# 03-mcu1.net
KiCad netlist of a schematic drawn in Altium Designer
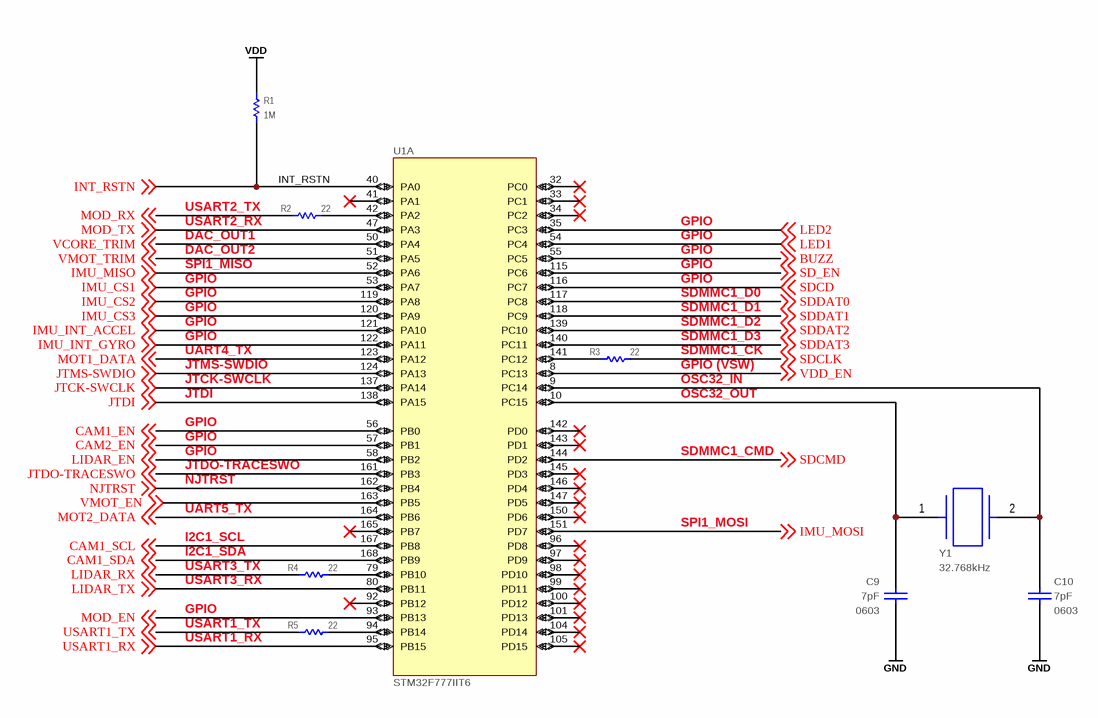
[diagram p0: 03-mcu1.SchDoc]

(export (version "E")
  (design (tool "Eeschema 10.0.6"))
  (components
    (comp (ref "C9")
      (value "7pF")
      (footprint "generic:CAPC160X80X90L20N")
      (description "Ceramic Capacitor 7pF +/-0.25pF 0603")
      (fields
        (field (name "MANUFACTURER") "Samsung")
        (field (name "TOLERANCE") "+/-0.25pF")
        (field (name "PACKAGE") "0603")
      )
      (libsource (lib "vishay") (part "CAP"))
    )
    (comp (ref "C10")
      (value "7pF")
      (footprint "generic:CAPC160X80X90L20N")
      (description "Ceramic Capacitor 7pF +/-0.25pF 0603")
      (fields
        (field (name "MANUFACTURER") "Samsung")
        (field (name "TOLERANCE") "+/-0.25pF")
        (field (name "PACKAGE") "0603")
      )
      (libsource (lib "vishay") (part "CAP"))
    )
    (comp (ref "R1")
      (value "1M")
      (footprint "RESC2012X70N")
      (description "Thick Film Resistor 1M ±1% 0805")
      (fields (field (name "MANUFACTURER") "Panasonic") (field (name "TOLERANCE") "±1%"))
      (libsource (lib "Graviton") (part "RES 0402"))
    )
    (comp (ref "R2")
      (value "22")
      (footprint "RESC2012X70N")
      (description "Thick Film Resistor 22 ±1% 0805")
      (fields (field (name "MANUFACTURER") "Panasonic") (field (name "TOLERANCE") "±1%"))
      (libsource (lib "Graviton") (part "RES 0402"))
    )
    (comp (ref "R3")
      (value "22")
      (footprint "RESC2012X70N")
      (description "Thick Film Resistor 22 ±1% 0805")
      (fields (field (name "MANUFACTURER") "Panasonic") (field (name "TOLERANCE") "±1%"))
      (libsource (lib "Graviton") (part "RES 0402"))
    )
    (comp (ref "R4")
      (value "22")
      (footprint "RESC2012X70N")
      (description "Thick Film Resistor 22 ±1% 0805")
      (fields (field (name "MANUFACTURER") "Panasonic") (field (name "TOLERANCE") "±1%"))
      (libsource (lib "Graviton") (part "RES 0402"))
    )
    (comp (ref "R5")
      (value "22")
      (footprint "RESC2012X70N")
      (description "Thick Film Resistor 22 ±1% 0805")
      (fields (field (name "MANUFACTURER") "Panasonic") (field (name "TOLERANCE") "±1%"))
      (libsource (lib "Graviton") (part "RES 0402"))
    )
    (comp (ref "U1")
      (value "STM32F777IIT6")
      (footprint "st:TSQFP50P2600X2600X160-176N")
      (description "Microcontroller")
      (fields (field (name "MANUFACTURER") "STMicroelectronics"))
      (libsource (lib "st") (part "STM32F777IIT"))
    )
    (comp (ref "Y1")
      (value "ABS07-32.768KHZ-7")
      (footprint "ABS07")
      (description "CRYSTAL 32.7680KHZ 7PF SMD")
      (fields (field (name "MANUFACTURER") "Abracon LLC") (field (name "FREQUENCY") "32.768kHz"))
      (libsource (lib "abracon") (part "ABS07-32.768KHZ-7"))
    )
  )
  (nets
    (net (code "1") (name "BUZZ") (class "Default")
      (node (ref "U1") (pin "55") (pinfunction "PC5_55") (pintype "bidirectional"))
    )
    (net (code "2") (name "CAM1_EN") (class "Default")
      (node (ref "U1") (pin "56") (pinfunction "PB0_56") (pintype "bidirectional"))
    )
    (net (code "3") (name "CAM1_SCL") (class "Default")
      (node (ref "U1") (pin "167") (pinfunction "PB8_167") (pintype "bidirectional"))
    )
    (net (code "4") (name "CAM1_SDA") (class "Default")
      (node (ref "U1") (pin "168") (pinfunction "PB9_168") (pintype "bidirectional"))
    )
    (net (code "5") (name "CAM2_EN") (class "Default")
      (node (ref "U1") (pin "57") (pinfunction "PB1_57") (pintype "bidirectional"))
    )
    (net (code "6") (name "GND") (class "Default")
      (node (ref "C10") (pin "1") (pinfunction "1_1") (pintype "passive"))
      (node (ref "C9") (pin "1") (pinfunction "1_1") (pintype "passive"))
    )
    (net (code "7") (name "IMU_CS1") (class "Default")
      (node (ref "U1") (pin "53") (pinfunction "PA7_53") (pintype "bidirectional"))
    )
    (net (code "8") (name "IMU_CS2") (class "Default")
      (node (ref "U1") (pin "119") (pinfunction "PA8_119") (pintype "bidirectional"))
    )
    (net (code "9") (name "IMU_CS3") (class "Default")
      (node (ref "U1") (pin "120") (pinfunction "PA9_120") (pintype "bidirectional"))
    )
    (net (code "10") (name "IMU_INT_ACCEL") (class "Default")
      (node (ref "U1") (pin "121") (pinfunction "PA10_121") (pintype "bidirectional"))
    )
    (net (code "11") (name "IMU_INT_GYRO") (class "Default")
      (node (ref "U1") (pin "122") (pinfunction "PA11_122") (pintype "bidirectional"))
    )
    (net (code "12") (name "IMU_MISO") (class "Default")
      (node (ref "U1") (pin "52") (pinfunction "PA6_52") (pintype "bidirectional"))
    )
    (net (code "13") (name "IMU_MOSI") (class "Default")
      (node (ref "U1") (pin "151") (pinfunction "PD7_151") (pintype "bidirectional"))
    )
    (net (code "14") (name "INT_RSTN") (class "Default")
      (node (ref "R1") (pin "1") (pinfunction "1_1") (pintype "passive"))
      (node (ref "U1") (pin "40") (pinfunction "PA0_40") (pintype "bidirectional"))
    )
    (net (code "15") (name "JTCK-SWCLK") (class "Default")
      (node (ref "U1") (pin "137") (pinfunction "PA14_137") (pintype "bidirectional"))
    )
    (net (code "16") (name "JTDI") (class "Default")
      (node (ref "U1") (pin "138") (pinfunction "PA15_138") (pintype "bidirectional"))
    )
    (net (code "17") (name "JTDO-TRACESWO") (class "Default")
      (node (ref "U1") (pin "161") (pinfunction "PB3_161") (pintype "bidirectional"))
    )
    (net (code "18") (name "JTMS-SWDIO") (class "Default")
      (node (ref "U1") (pin "124") (pinfunction "PA13_124") (pintype "bidirectional"))
    )
    (net (code "19") (name "LED1") (class "Default")
      (node (ref "U1") (pin "54") (pinfunction "PC4_54") (pintype "bidirectional"))
    )
    (net (code "20") (name "LED2") (class "Default")
      (node (ref "U1") (pin "35") (pinfunction "PC3_35") (pintype "bidirectional"))
    )
    (net (code "21") (name "LIDAR_EN") (class "Default")
      (node (ref "U1") (pin "58") (pinfunction "PB2_58") (pintype "bidirectional"))
    )
    (net (code "22") (name "LIDAR_RX") (class "Default")
      (node (ref "R4") (pin "2") (pinfunction "2_2") (pintype "passive"))
    )
    (net (code "23") (name "LIDAR_TX") (class "Default")
      (node (ref "U1") (pin "80") (pinfunction "PB11_80") (pintype "bidirectional"))
    )
    (net (code "24") (name "MOD_EN") (class "Default")
      (node (ref "U1") (pin "93") (pinfunction "PB13_93") (pintype "bidirectional"))
    )
    (net (code "25") (name "MOD_RX") (class "Default")
      (node (ref "R2") (pin "2") (pinfunction "2_2") (pintype "passive"))
    )
    (net (code "26") (name "MOD_TX") (class "Default")
      (node (ref "U1") (pin "47") (pinfunction "PA3_47") (pintype "bidirectional"))
    )
    (net (code "27") (name "MOT1_DATA") (class "Default")
      (node (ref "U1") (pin "123") (pinfunction "PA12_123") (pintype "bidirectional"))
    )
    (net (code "28") (name "MOT2_DATA") (class "Default")
      (node (ref "U1") (pin "164") (pinfunction "PB6_164") (pintype "bidirectional"))
    )
    (net (code "29") (name "NJTRST") (class "Default")
      (node (ref "U1") (pin "162") (pinfunction "PB4_162") (pintype "bidirectional"))
    )
    (net (code "30") (name "Net-(U1A-PA2)") (class "Default")
      (node (ref "R2") (pin "1") (pinfunction "1_1") (pintype "passive"))
      (node (ref "U1") (pin "42") (pinfunction "PA2_42") (pintype "bidirectional"))
    )
    (net (code "31") (name "Net-(U1A-PB10)") (class "Default")
      (node (ref "R4") (pin "1") (pinfunction "1_1") (pintype "passive"))
      (node (ref "U1") (pin "79") (pinfunction "PB10_79") (pintype "bidirectional"))
    )
    (net (code "32") (name "Net-(U1A-PB14)") (class "Default")
      (node (ref "R5") (pin "1") (pinfunction "1_1") (pintype "passive"))
      (node (ref "U1") (pin "94") (pinfunction "PB14_94") (pintype "bidirectional"))
    )
    (net (code "33") (name "Net-(U1A-PC12)") (class "Default")
      (node (ref "R3") (pin "2") (pinfunction "2_2") (pintype "passive"))
      (node (ref "U1") (pin "141") (pinfunction "PC12_141") (pintype "bidirectional"))
    )
    (net (code "34") (name "Net-(U1A-PC14)") (class "Default")
      (node (ref "C10") (pin "2") (pinfunction "2_2") (pintype "passive"))
      (node (ref "U1") (pin "9") (pinfunction "PC14_9") (pintype "bidirectional"))
      (node (ref "Y1") (pin "2") (pinfunction "XTAL2_2") (pintype "passive"))
    )
    (net (code "35") (name "Net-(U1A-PC15)") (class "Default")
      (node (ref "C9") (pin "2") (pinfunction "2_2") (pintype "passive"))
      (node (ref "U1") (pin "10") (pinfunction "PC15_10") (pintype "bidirectional"))
      (node (ref "Y1") (pin "1") (pinfunction "XTAL1_1") (pintype "passive"))
    )
    (net (code "36") (name "SDCD") (class "Default")
      (node (ref "U1") (pin "116") (pinfunction "PC7_116") (pintype "bidirectional"))
    )
    (net (code "37") (name "SDCLK") (class "Default")
      (node (ref "R3") (pin "1") (pinfunction "1_1") (pintype "passive"))
    )
    (net (code "38") (name "SDCMD") (class "Default")
      (node (ref "U1") (pin "144") (pinfunction "PD2_144") (pintype "bidirectional"))
    )
    (net (code "39") (name "SDDAT0") (class "Default")
      (node (ref "U1") (pin "117") (pinfunction "PC8_117") (pintype "bidirectional"))
    )
    (net (code "40") (name "SDDAT1") (class "Default")
      (node (ref "U1") (pin "118") (pinfunction "PC9_118") (pintype "bidirectional"))
    )
    (net (code "41") (name "SDDAT2") (class "Default")
      (node (ref "U1") (pin "139") (pinfunction "PC10_139") (pintype "bidirectional"))
    )
    (net (code "42") (name "SDDAT3") (class "Default")
      (node (ref "U1") (pin "140") (pinfunction "PC11_140") (pintype "bidirectional"))
    )
    (net (code "43") (name "SD_EN") (class "Default")
      (node (ref "U1") (pin "115") (pinfunction "PC6_115") (pintype "bidirectional"))
    )
    (net (code "44") (name "USART1_RX") (class "Default")
      (node (ref "U1") (pin "95") (pinfunction "PB15_95") (pintype "bidirectional"))
    )
    (net (code "45") (name "USART1_TX") (class "Default")
      (node (ref "R5") (pin "2") (pinfunction "2_2") (pintype "passive"))
    )
    (net (code "46") (name "VCORE_TRIM") (class "Default")
      (node (ref "U1") (pin "50") (pinfunction "PA4_50") (pintype "bidirectional"))
    )
    (net (code "47") (name "VDD") (class "Default")
      (node (ref "R1") (pin "2") (pinfunction "2_2") (pintype "passive"))
    )
    (net (code "48") (name "VDD_EN") (class "Default")
      (node (ref "U1") (pin "8") (pinfunction "PC13_8") (pintype "bidirectional"))
    )
    (net (code "49") (name "VMOT_EN") (class "Default")
      (node (ref "U1") (pin "163") (pinfunction "PB5_163") (pintype "bidirectional"))
    )
    (net (code "50") (name "VMOT_TRIM") (class "Default")
      (node (ref "U1") (pin "51") (pinfunction "PA5_51") (pintype "bidirectional"))
    )
    (net (code "51") (name "unconnected-(U1A-PA1-Pad41)") (class "Default")
      (node (ref "U1") (pin "41") (pinfunction "PA1_41") (pintype "bidirectional+no_connect"))
    )
    (net (code "52") (name "unconnected-(U1A-PB7-Pad165)") (class "Default")
      (node (ref "U1") (pin "165") (pinfunction "PB7_165") (pintype "bidirectional+no_connect"))
    )
    (net (code "53") (name "unconnected-(U1A-PB12-Pad92)") (class "Default")
      (node (ref "U1") (pin "92") (pinfunction "PB12_92") (pintype "bidirectional+no_connect"))
    )
    (net (code "54") (name "unconnected-(U1A-PC0-Pad32)") (class "Default")
      (node (ref "U1") (pin "32") (pinfunction "PC0_32") (pintype "bidirectional+no_connect"))
    )
    (net (code "55") (name "unconnected-(U1A-PC1-Pad33)") (class "Default")
      (node (ref "U1") (pin "33") (pinfunction "PC1_33") (pintype "bidirectional+no_connect"))
    )
    (net (code "56") (name "unconnected-(U1A-PC2-Pad34)") (class "Default")
      (node (ref "U1") (pin "34") (pinfunction "PC2_34") (pintype "bidirectional+no_connect"))
    )
    (net (code "57") (name "unconnected-(U1A-PD0-Pad142)") (class "Default")
      (node (ref "U1") (pin "142") (pinfunction "PD0_142") (pintype "bidirectional+no_connect"))
    )
    (net (code "58") (name "unconnected-(U1A-PD1-Pad143)") (class "Default")
      (node (ref "U1") (pin "143") (pinfunction "PD1_143") (pintype "bidirectional+no_connect"))
    )
    (net (code "59") (name "unconnected-(U1A-PD3-Pad145)") (class "Default")
      (node (ref "U1") (pin "145") (pinfunction "PD3_145") (pintype "bidirectional+no_connect"))
    )
    (net (code "60") (name "unconnected-(U1A-PD4-Pad146)") (class "Default")
      (node (ref "U1") (pin "146") (pinfunction "PD4_146") (pintype "bidirectional+no_connect"))
    )
    (net (code "61") (name "unconnected-(U1A-PD5-Pad147)") (class "Default")
      (node (ref "U1") (pin "147") (pinfunction "PD5_147") (pintype "bidirectional+no_connect"))
    )
    (net (code "62") (name "unconnected-(U1A-PD6-Pad150)") (class "Default")
      (node (ref "U1") (pin "150") (pinfunction "PD6_150") (pintype "bidirectional+no_connect"))
    )
    (net (code "63") (name "unconnected-(U1A-PD8-Pad96)") (class "Default")
      (node (ref "U1") (pin "96") (pinfunction "PD8_96") (pintype "bidirectional+no_connect"))
    )
    (net (code "64") (name "unconnected-(U1A-PD9-Pad97)") (class "Default")
      (node (ref "U1") (pin "97") (pinfunction "PD9_97") (pintype "bidirectional+no_connect"))
    )
    (net (code "65") (name "unconnected-(U1A-PD10-Pad98)") (class "Default")
      (node (ref "U1") (pin "98") (pinfunction "PD10_98") (pintype "bidirectional+no_connect"))
    )
    (net (code "66") (name "unconnected-(U1A-PD11-Pad99)") (class "Default")
      (node (ref "U1") (pin "99") (pinfunction "PD11_99") (pintype "bidirectional+no_connect"))
    )
    (net (code "67") (name "unconnected-(U1A-PD12-Pad100)") (class "Default")
      (node (ref "U1") (pin "100") (pinfunction "PD12_100") (pintype "bidirectional+no_connect"))
    )
    (net (code "68") (name "unconnected-(U1A-PD13-Pad101)") (class "Default")
      (node (ref "U1") (pin "101") (pinfunction "PD13_101") (pintype "bidirectional+no_connect"))
    )
    (net (code "69") (name "unconnected-(U1A-PD14-Pad104)") (class "Default")
      (node (ref "U1") (pin "104") (pinfunction "PD14_104") (pintype "bidirectional+no_connect"))
    )
    (net (code "70") (name "unconnected-(U1A-PD15-Pad105)") (class "Default")
      (node (ref "U1") (pin "105") (pinfunction "PD15_105") (pintype "bidirectional+no_connect"))
    )
  )
)
